# DDR_TERM_PWR.net
KiCad netlist of a schematic drawn in Altium Designer
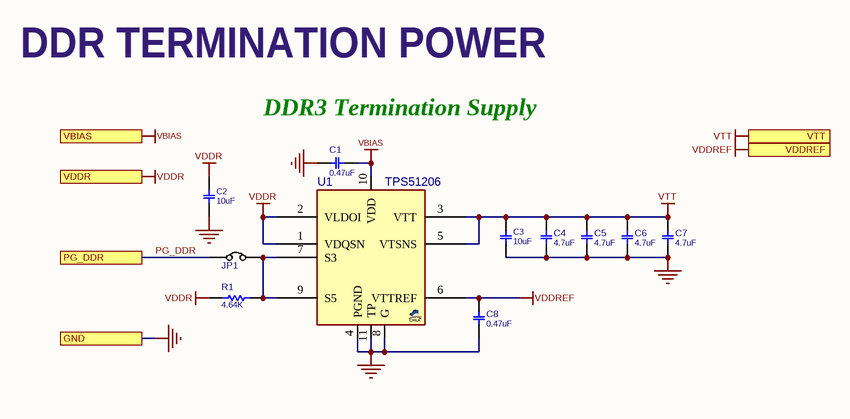
[diagram p0: DDR_TERM_PWR.SchDoc]

(export (version "E")
  (design (tool "Eeschema 10.0.6"))
  (components
    (comp (ref "C1")
      (value "0.47uF")
      (footprint "C0402")
      (description "CAP, MLCC, 100nF, 50V, X7S, 5%, 0402C")
      (fields (field (name "MANF_PART#") "GRM155C71H104JE19D") (field (name "MANF") "Murata"))
      (libsource (lib "passive_mlcc_smd") (part "CAP_SMD_MLCC_100n50V"))
    )
    (comp (ref "C2")
      (value "10uF")
      (footprint "C0402")
      (description "CAP, MLCC")
      (fields (field (name "MANF") "Taiyo Yuden"))
      (libsource (lib "mlcc_smd_passive") (part "CAP_SMD_MLCC_100n50T"))
    )
    (comp (ref "C3")
      (value "10uF")
      (footprint "C0402")
      (description "CAP, MLCC")
      (fields (field (name "MANF") "Taiyo Yuden"))
      (libsource (lib "mlcc_smd_passive") (part "CAP_SMD_MLCC_100n50T"))
    )
    (comp (ref "C4")
      (value "4.7uF")
      (footprint "C0402")
      (description "CAP, MLCC")
      (fields (field (name "MANF_PART#") "GRM155C71H104JE19D") (field (name "MANF") "Murata"))
      (libsource (lib "passive_mlcc_smd") (part "CAP_SMD_MLCC_100n50V"))
    )
    (comp (ref "C5")
      (value "4.7uF")
      (footprint "C0402")
      (description "CAP, MLCC")
      (fields (field (name "MANF_PART#") "GRM155C71H104JE19D") (field (name "MANF") "Murata"))
      (libsource (lib "passive_mlcc_smd") (part "CAP_SMD_MLCC_100n50V"))
    )
    (comp (ref "C6")
      (value "4.7uF")
      (footprint "C0402")
      (description "CAP, MLCC")
      (fields (field (name "MANF_PART#") "GRM155C71H104JE19D") (field (name "MANF") "Murata"))
      (libsource (lib "passive_mlcc_smd") (part "CAP_SMD_MLCC_100n50V"))
    )
    (comp (ref "C7")
      (value "4.7uF")
      (footprint "C0402")
      (description "CAP, MLCC")
      (fields (field (name "MANF_PART#") "GRM155C71H104JE19D") (field (name "MANF") "Murata"))
      (libsource (lib "passive_mlcc_smd") (part "CAP_SMD_MLCC_100n50V"))
    )
    (comp (ref "C8")
      (value "0.47uF")
      (footprint "C0402")
      (description "CAP, MLCC, 100nF, 50V, X7S, 5%, 0402C")
      (fields (field (name "MANF_PART#") "GRM155C71H104JE19D") (field (name "MANF") "Murata"))
      (libsource (lib "passive_mlcc_smd") (part "CAP_SMD_MLCC_100n50V"))
    )
    (comp (ref "JP1")
      (value "JMPSOLDER")
      (footprint "JP_60X100")
      (description "JUMPER, HEADER 2PIN")
      (fields (field (name "MANF") "MANF") (field (name "MANF_P#") "MANF_P#"))
      (libsource (lib "test-tp_jumper") (part "JUMPER_SOLDER"))
    )
    (comp (ref "R1")
      (value "4.64K")
      (footprint "R0402")
      (description "RESISTOR, SMD, 10K, 1%, 0402")
      (fields (field (name "MANF") "KOA SPEER") (field (name "MANF_P#") "RK73H1ETTP1002F"))
      (libsource (lib "chila_passive") (part "RES_SMD"))
    )
    (comp (ref "U1")
      (value "TPS51206")
      (footprint "SON40_10T_2020")
      (description "REG, Linear, LDO, 2A Sink/Source DDR Termination, SON-10")
      (fields (field (name "MANF") "TI") (field (name "MANF_P#") "TPS51206DSQ"))
      (libsource (lib "reg_DDR") (part "VREG_TPS51206_SON10"))
    )
  )
  (nets
    (net (code "1") (name "/PG_DDR") (class "Default")
      (node (ref "JP1") (pin "1") (pinfunction "1_1") (pintype "passive"))
    )
    (net (code "2") (name "GND") (class "Default")
      (node (ref "C1") (pin "2") (pinfunction "2_2") (pintype "passive"))
      (node (ref "C2") (pin "2") (pinfunction "2_2") (pintype "passive"))
      (node (ref "C3") (pin "2") (pinfunction "2_2") (pintype "passive"))
      (node (ref "C4") (pin "2") (pinfunction "2_2") (pintype "passive"))
      (node (ref "C5") (pin "2") (pinfunction "2_2") (pintype "passive"))
      (node (ref "C6") (pin "2") (pinfunction "2_2") (pintype "passive"))
      (node (ref "C7") (pin "2") (pinfunction "2_2") (pintype "passive"))
      (node (ref "C8") (pin "2") (pinfunction "2_2") (pintype "passive"))
      (node (ref "U1") (pin "11") (pinfunction "TP_11") (pintype "passive"))
      (node (ref "U1") (pin "4") (pinfunction "PGND_4") (pintype "passive"))
      (node (ref "U1") (pin "8") (pinfunction "G_8") (pintype "passive"))
    )
    (net (code "3") (name "Net-(U1-S3)") (class "Default")
      (node (ref "JP1") (pin "2") (pinfunction "2_2") (pintype "passive"))
      (node (ref "R1") (pin "2") (pinfunction "2_2") (pintype "passive"))
      (node (ref "U1") (pin "7") (pinfunction "S3_7") (pintype "passive"))
      (node (ref "U1") (pin "9") (pinfunction "S5_9") (pintype "passive"))
    )
    (net (code "4") (name "VBIAS") (class "Default")
      (node (ref "C1") (pin "1") (pinfunction "1_1") (pintype "passive"))
      (node (ref "U1") (pin "10") (pinfunction "VDD_10") (pintype "passive"))
    )
    (net (code "5") (name "VDDR") (class "Default")
      (node (ref "C2") (pin "1") (pinfunction "1_1") (pintype "passive"))
      (node (ref "R1") (pin "1") (pinfunction "1_1") (pintype "passive"))
      (node (ref "U1") (pin "1") (pinfunction "VDQSN_1") (pintype "passive"))
      (node (ref "U1") (pin "2") (pinfunction "VLDOI_2") (pintype "passive"))
    )
    (net (code "6") (name "VDDREF") (class "Default")
      (node (ref "C8") (pin "1") (pinfunction "1_1") (pintype "passive"))
      (node (ref "U1") (pin "6") (pinfunction "VTTREF_6") (pintype "passive"))
    )
    (net (code "7") (name "VTT") (class "Default")
      (node (ref "C3") (pin "1") (pinfunction "1_1") (pintype "passive"))
      (node (ref "C4") (pin "1") (pinfunction "1_1") (pintype "passive"))
      (node (ref "C5") (pin "1") (pinfunction "1_1") (pintype "passive"))
      (node (ref "C6") (pin "1") (pinfunction "1_1") (pintype "passive"))
      (node (ref "C7") (pin "1") (pinfunction "1_1") (pintype "passive"))
      (node (ref "U1") (pin "3") (pinfunction "VTT_3") (pintype "passive"))
      (node (ref "U1") (pin "5") (pinfunction "VTSNS_5") (pintype "passive"))
    )
  )
)
